# uMultimeter_PROBE_Sch.net
KiCad netlist of a schematic drawn in Altium Designer
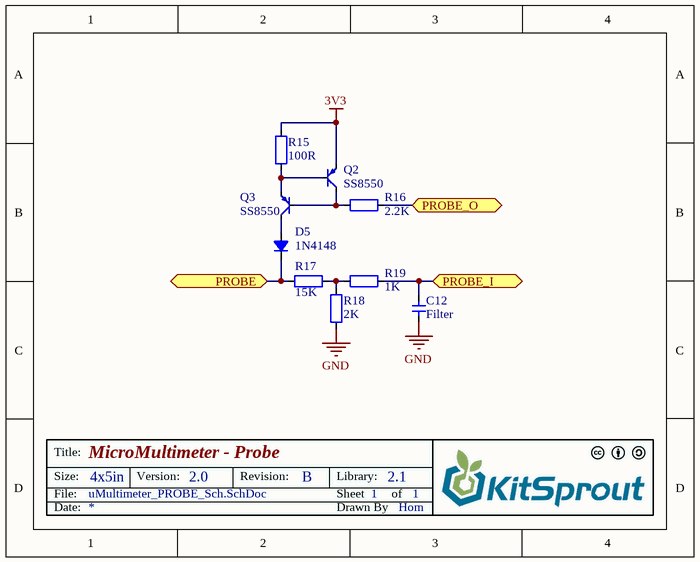
[diagram p0: uMultimeter_PROBE_Sch.SchDoc]

(export (version "E")
  (design (tool "Eeschema 10.0.6"))
  (components
    (comp (ref "C12")
      (value "Filter")
      (footprint "PCB_PassiveCap:CAP_0603")
      (description "Capacitor")
      (fields (field (name "Comment") "Cap_0603"))
      (libsource (lib "SCH_Passive") (part "Cap_0603"))
    )
    (comp (ref "D5")
      (value "1N4148")
      (footprint "PCB_ActiveDIO:SOD-323")
      (description "Diode")
      (fields (field (name "Comment") "Diode_SOD323"))
      (libsource (lib "SCH_Active") (part "Diode_SOD323"))
    )
    (comp (ref "Q2")
      (value "SS8550")
      (footprint "PCB_IntegratedCircuit:SOT23-3")
      (description "Transistor")
      (fields (field (name "Comment") "BJT_PNP"))
      (libsource (lib "SCH_Active") (part "BJT_PNP"))
    )
    (comp (ref "Q3")
      (value "SS8550")
      (footprint "PCB_IntegratedCircuit:SOT23-3")
      (description "Transistor")
      (fields (field (name "Comment") "BJT_PNP"))
      (libsource (lib "SCH_Active") (part "BJT_PNP"))
    )
    (comp (ref "R15")
      (value "100R")
      (footprint "PCB_PassiveRes:RES_0603")
      (description "Resistor")
      (fields (field (name "Comment") "Res_0603"))
      (libsource (lib "") (part "Res_0603_3"))
    )
    (comp (ref "R16")
      (value "2.2K")
      (footprint "PCB_PassiveRes:RES_0603")
      (description "Resistor")
      (fields (field (name "Comment") "Res_0603"))
      (libsource (lib "SCH_Passive") (part "Res_0603"))
    )
    (comp (ref "R17")
      (value "15K")
      (footprint "PCB_PassiveRes:RES_0603")
      (description "Resistor")
      (fields (field (name "Comment") "Res_0603"))
      (libsource (lib "SCH_Passive") (part "Res_0603"))
    )
    (comp (ref "R18")
      (value "2K")
      (footprint "PCB_PassiveRes:RES_0603")
      (description "Resistor")
      (fields (field (name "Comment") "Res_0603"))
      (libsource (lib "") (part "Res_0603_2"))
    )
    (comp (ref "R19")
      (value "1K")
      (footprint "PCB_PassiveRes:RES_0603")
      (description "Resistor")
      (fields (field (name "Comment") "Res_0603"))
      (libsource (lib "") (part "Res_0603_1"))
    )
  )
  (nets
    (net (code "1") (name "/PROBE") (class "Default")
      (node (ref "D5") (pin "2") (pinfunction "K_2") (pintype "passive"))
      (node (ref "R17") (pin "2") (pinfunction "2_2") (pintype "passive"))
    )
    (net (code "2") (name "/PROBE_I") (class "Default")
      (node (ref "C12") (pin "2") (pinfunction "2_2") (pintype "passive"))
      (node (ref "R19") (pin "2") (pinfunction "2_2") (pintype "passive"))
    )
    (net (code "3") (name "/PROBE_O") (class "Default")
      (node (ref "R16") (pin "1") (pinfunction "1_1") (pintype "passive"))
    )
    (net (code "4") (name "3V3") (class "Default")
      (node (ref "Q2") (pin "2") (pinfunction "E_2") (pintype "passive"))
      (node (ref "R15") (pin "2") (pinfunction "2_2") (pintype "passive"))
    )
    (net (code "5") (name "GND") (class "Default")
      (node (ref "C12") (pin "1") (pinfunction "1_1") (pintype "passive"))
      (node (ref "R18") (pin "2") (pinfunction "2_2") (pintype "passive"))
    )
    (net (code "6") (name "Net-(D5-A)") (class "Default")
      (node (ref "D5") (pin "1") (pinfunction "A_1") (pintype "passive"))
      (node (ref "Q3") (pin "3") (pinfunction "C_3") (pintype "passive"))
    )
    (net (code "7") (name "Net-(Q2-B)") (class "Default")
      (node (ref "Q2") (pin "1") (pinfunction "B_1") (pintype "passive"))
      (node (ref "Q3") (pin "2") (pinfunction "E_2") (pintype "passive"))
      (node (ref "R15") (pin "1") (pinfunction "1_1") (pintype "passive"))
    )
    (net (code "8") (name "Net-(Q2-C)") (class "Default")
      (node (ref "Q2") (pin "3") (pinfunction "C_3") (pintype "passive"))
      (node (ref "Q3") (pin "1") (pinfunction "B_1") (pintype "passive"))
      (node (ref "R16") (pin "2") (pinfunction "2_2") (pintype "passive"))
    )
    (net (code "9") (name "Net-(R17-Pad1)") (class "Default")
      (node (ref "R17") (pin "1") (pinfunction "1_1") (pintype "passive"))
      (node (ref "R18") (pin "1") (pinfunction "1_1") (pintype "passive"))
      (node (ref "R19") (pin "1") (pinfunction "1_1") (pintype "passive"))
    )
  )
)
